# Audio_SCHEMATIC.net
KiCad netlist of a schematic drawn in Altium Designer
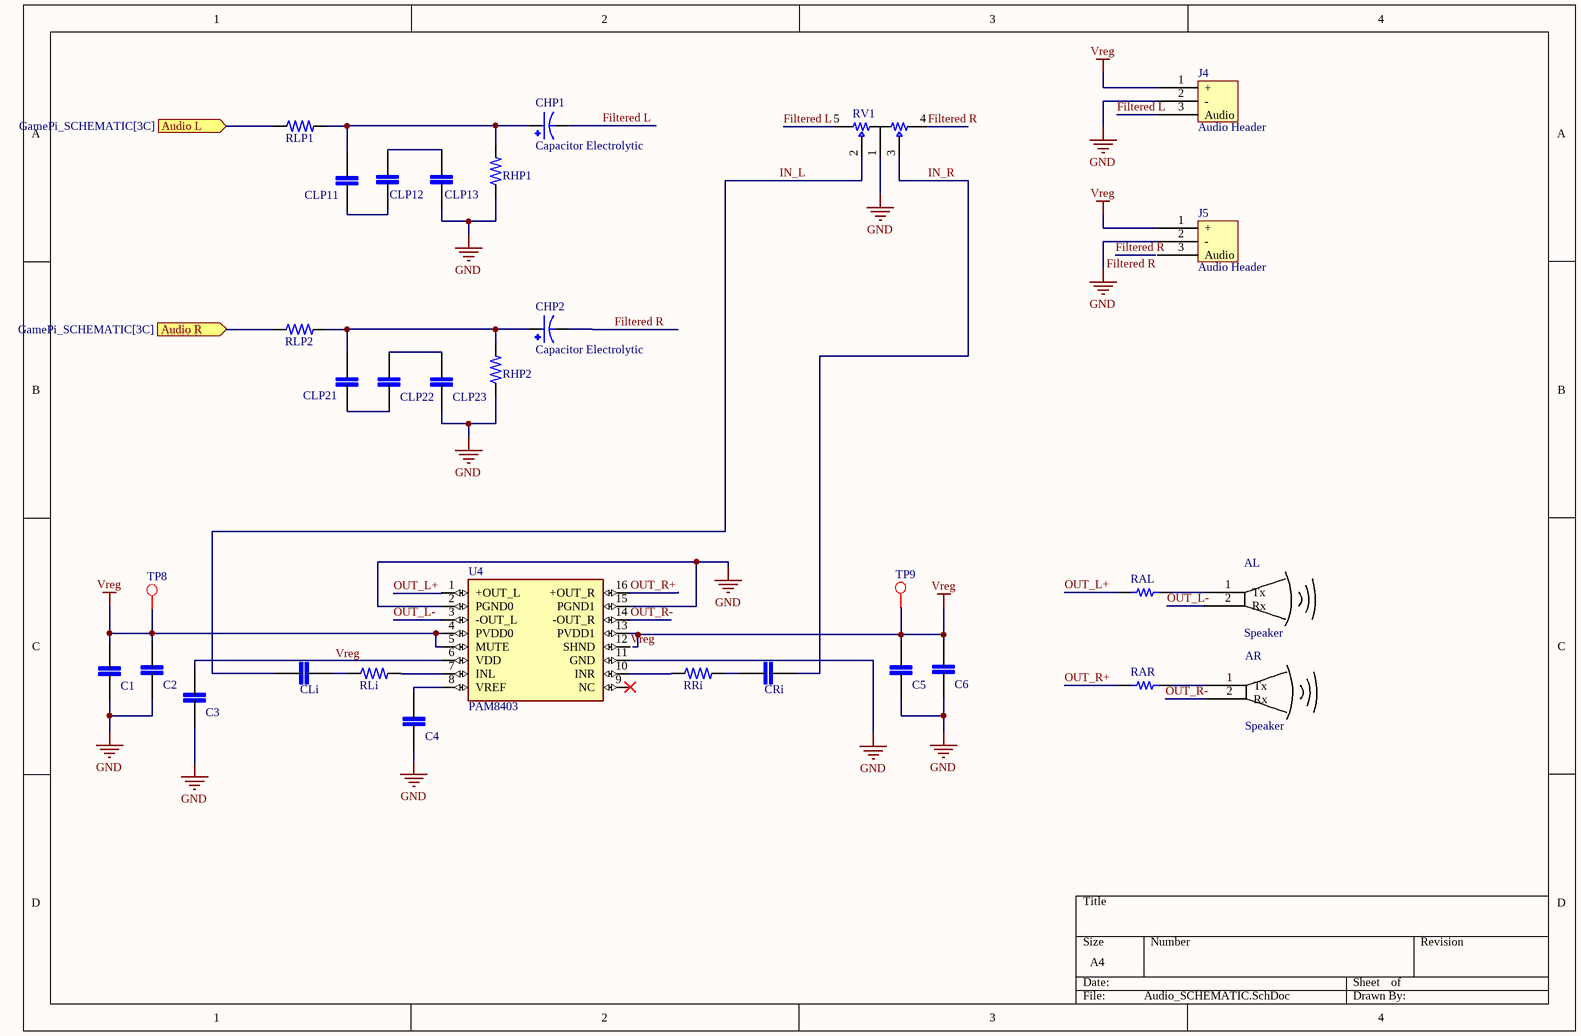
[diagram p0: Audio_SCHEMATIC.SchDoc]

(export (version "E")
  (design (tool "Eeschema 10.0.6"))
  (components
    (comp (ref "AL")
      (value "Speaker")
      (footprint "Speaker")
      (libsource (lib "GamePi SCH LIB") (part "Speaker"))
    )
    (comp (ref "AR")
      (value "Speaker")
      (footprint "Speaker")
      (libsource (lib "GamePi SCH LIB") (part "Speaker"))
    )
    (comp (ref "C1")
      (value "0805")
      (footprint "Capacitor 0805")
      (libsource (lib "GamePi SCH LIB") (part "Capacitor 0805"))
    )
    (comp (ref "C2")
      (value "0805")
      (footprint "Capacitor 0805")
      (libsource (lib "GamePi SCH LIB") (part "Capacitor 0805"))
    )
    (comp (ref "C3")
      (value "0805")
      (footprint "Capacitor 0805")
      (libsource (lib "GamePi SCH LIB") (part "Capacitor 0805"))
    )
    (comp (ref "C4")
      (value "0805")
      (footprint "Capacitor 0805")
      (libsource (lib "GamePi SCH LIB") (part "Capacitor 0805"))
    )
    (comp (ref "C5")
      (value "0805")
      (footprint "Capacitor 0805")
      (libsource (lib "GamePi SCH LIB") (part "Capacitor 0805"))
    )
    (comp (ref "C6")
      (value "0805")
      (footprint "Capacitor 0805")
      (libsource (lib "GamePi SCH LIB") (part "Capacitor 0805"))
    )
    (comp (ref "CHP1")
      (value "Capacitor Electrolytic")
      (footprint "Capacitor Electrolytic")
      (libsource (lib "GamePi SCH LIB") (part "Capacitor Electrolytic"))
    )
    (comp (ref "CHP2")
      (value "Capacitor Electrolytic")
      (footprint "Capacitor Electrolytic")
      (libsource (lib "GamePi SCH LIB") (part "Capacitor Electrolytic"))
    )
    (comp (ref "CLi")
      (value "0805")
      (footprint "Capacitor 0805")
      (libsource (lib "GamePi") (part "Capacitor 0805"))
    )
    (comp (ref "CLP11")
      (value "0805")
      (footprint "Capacitor 0805")
      (libsource (lib "GamePi SCH LIB") (part "Capacitor 0805"))
    )
    (comp (ref "CLP12")
      (value "0805")
      (footprint "Capacitor 0805")
      (libsource (lib "GamePi SCH LIB") (part "Capacitor 0805"))
    )
    (comp (ref "CLP13")
      (value "0805")
      (footprint "Capacitor 0805")
      (libsource (lib "GamePi SCH LIB") (part "Capacitor 0805"))
    )
    (comp (ref "CLP21")
      (value "0805")
      (footprint "Capacitor 0805")
      (libsource (lib "GamePi SCH LIB") (part "Capacitor 0805"))
    )
    (comp (ref "CLP22")
      (value "0805")
      (footprint "Capacitor 0805")
      (libsource (lib "GamePi SCH LIB") (part "Capacitor 0805"))
    )
    (comp (ref "CLP23")
      (value "0805")
      (footprint "Capacitor 0805")
      (libsource (lib "GamePi SCH LIB") (part "Capacitor 0805"))
    )
    (comp (ref "CRi")
      (value "0805")
      (footprint "Capacitor 0805")
      (libsource (lib "GamePi") (part "Capacitor 0805"))
    )
    (comp (ref "J4")
      (value "Audio Header")
      (footprint "Audio Header")
      (libsource (lib "GamePi SCH LIB") (part "Audio Header"))
    )
    (comp (ref "J5")
      (value "Audio Header")
      (footprint "Audio Header")
      (libsource (lib "GamePi SCH LIB") (part "Audio Header"))
    )
    (comp (ref "RAL")
      (value "Resistor Axial")
      (footprint "Resistor Axial")
      (libsource (lib "GamePi SCH LIB") (part "Resistor Axial"))
    )
    (comp (ref "RAR")
      (value "Resistor Axial")
      (footprint "Resistor Axial")
      (libsource (lib "GamePi SCH LIB") (part "Resistor Axial"))
    )
    (comp (ref "RHP1")
      (value "0805")
      (footprint "Resistor 0805")
      (libsource (lib "GamePi SCH LIB") (part "Resistor 0805"))
    )
    (comp (ref "RHP2")
      (value "0805")
      (footprint "Resistor 0805")
      (libsource (lib "GamePi SCH LIB") (part "Resistor 0805"))
    )
    (comp (ref "RLi")
      (value "0805")
      (footprint "Resistor 0805")
      (libsource (lib "GamePi") (part "Resistor 0805"))
    )
    (comp (ref "RLP1")
      (value "0805")
      (footprint "Resistor 0805")
      (libsource (lib "GamePi SCH LIB") (part "Resistor 0805"))
    )
    (comp (ref "RLP2")
      (value "0805")
      (footprint "Resistor 0805")
      (libsource (lib "GamePi SCH LIB") (part "Resistor 0805"))
    )
    (comp (ref "RRi")
      (value "0805")
      (footprint "Resistor 0805")
      (libsource (lib "GamePi") (part "Resistor 0805"))
    )
    (comp (ref "RV1")
      (value "B103 Potentiometer Wheel")
      (footprint "B103 Pot Wheel")
      (libsource (lib "GamePi SCH LIB") (part "B103 Potentiometer Wheel"))
    )
    (comp (ref "TP8")
      (value "Test Point")
      (footprint "Test Point")
      (libsource (lib "GamePi SCH LIB") (part "Test Point"))
    )
    (comp (ref "TP9")
      (value "Test Point")
      (footprint "Test Point")
      (libsource (lib "GamePi SCH LIB") (part "Test Point"))
    )
    (comp (ref "U4")
      (value "PAM8403")
      (footprint "PAM8403")
      (libsource (lib "GamePi SCH LIB") (part "PAM8403"))
    )
  )
  (nets
    (net (code "1") (name "/Audio L") (class "Default")
      (node (ref "RLP1") (pin "1") (pinfunction "1_1") (pintype "passive"))
    )
    (net (code "2") (name "/Audio R") (class "Default")
      (node (ref "RLP2") (pin "1") (pinfunction "1_1") (pintype "passive"))
    )
    (net (code "3") (name "/Filtered L") (class "Default")
      (node (ref "CHP1") (pin "N") (pinfunction "N_N") (pintype "passive"))
      (node (ref "J4") (pin "3") (pinfunction "Audio_3") (pintype "passive"))
      (node (ref "RV1") (pin "5") (pinfunction "5_5") (pintype "passive"))
    )
    (net (code "4") (name "/Filtered R") (class "Default")
      (node (ref "CHP2") (pin "N") (pinfunction "N_N") (pintype "passive"))
      (node (ref "J5") (pin "3") (pinfunction "Audio_3") (pintype "passive"))
      (node (ref "RV1") (pin "4") (pinfunction "4_4") (pintype "passive"))
    )
    (net (code "5") (name "/IN_L") (class "Default")
      (node (ref "CLi") (pin "1") (pinfunction "1_1") (pintype "passive"))
      (node (ref "RV1") (pin "2") (pinfunction "2_2") (pintype "passive"))
    )
    (net (code "6") (name "/IN_R") (class "Default")
      (node (ref "CRi") (pin "2") (pinfunction "2_2") (pintype "passive"))
      (node (ref "RV1") (pin "3") (pinfunction "3_3") (pintype "passive"))
    )
    (net (code "7") (name "/OUT_L+") (class "Default")
      (node (ref "RAL") (pin "1") (pinfunction "1_1") (pintype "passive"))
      (node (ref "U4") (pin "1") (pinfunction "+OUT_L_1") (pintype "bidirectional"))
    )
    (net (code "8") (name "/OUT_L-") (class "Default")
      (node (ref "AL") (pin "2") (pinfunction "Rx_2") (pintype "passive"))
      (node (ref "U4") (pin "3") (pinfunction "-OUT_L_3") (pintype "bidirectional"))
    )
    (net (code "9") (name "/OUT_R+") (class "Default")
      (node (ref "RAR") (pin "1") (pinfunction "1_1") (pintype "passive"))
      (node (ref "U4") (pin "16") (pinfunction "+OUT_R_16") (pintype "bidirectional"))
    )
    (net (code "10") (name "/OUT_R-") (class "Default")
      (node (ref "AR") (pin "2") (pinfunction "Rx_2") (pintype "passive"))
      (node (ref "U4") (pin "14") (pinfunction "-OUT_R_14") (pintype "bidirectional"))
    )
    (net (code "11") (name "GND") (class "Default")
      (node (ref "C1") (pin "1") (pinfunction "1_1") (pintype "passive"))
      (node (ref "C2") (pin "1") (pinfunction "1_1") (pintype "passive"))
      (node (ref "C3") (pin "1") (pinfunction "1_1") (pintype "passive"))
      (node (ref "C4") (pin "1") (pinfunction "1_1") (pintype "passive"))
      (node (ref "C5") (pin "1") (pinfunction "1_1") (pintype "passive"))
      (node (ref "C6") (pin "1") (pinfunction "1_1") (pintype "passive"))
      (node (ref "CLP13") (pin "1") (pinfunction "1_1") (pintype "passive"))
      (node (ref "CLP23") (pin "1") (pinfunction "1_1") (pintype "passive"))
      (node (ref "J4") (pin "2") (pinfunction "-_2") (pintype "passive"))
      (node (ref "J5") (pin "2") (pinfunction "-_2") (pintype "passive"))
      (node (ref "RHP1") (pin "1") (pinfunction "1_1") (pintype "passive"))
      (node (ref "RHP2") (pin "1") (pinfunction "1_1") (pintype "passive"))
      (node (ref "RV1") (pin "1") (pinfunction "1_1") (pintype "passive"))
      (node (ref "U4") (pin "11") (pinfunction "GND_11") (pintype "bidirectional"))
      (node (ref "U4") (pin "15") (pinfunction "PGND1_15") (pintype "bidirectional"))
      (node (ref "U4") (pin "2") (pinfunction "PGND0_2") (pintype "bidirectional"))
    )
    (net (code "12") (name "Net-(AL-Tx)") (class "Default")
      (node (ref "AL") (pin "1") (pinfunction "Tx_1") (pintype "passive"))
      (node (ref "RAL") (pin "2") (pinfunction "2_2") (pintype "passive"))
    )
    (net (code "13") (name "Net-(AR-Tx)") (class "Default")
      (node (ref "AR") (pin "1") (pinfunction "Tx_1") (pintype "passive"))
      (node (ref "RAR") (pin "2") (pinfunction "2_2") (pintype "passive"))
    )
    (net (code "14") (name "Net-(CHP1-PadP)") (class "Default")
      (node (ref "CHP1") (pin "P") (pinfunction "P_P") (pintype "passive"))
      (node (ref "CLP11") (pin "2") (pinfunction "2_2") (pintype "passive"))
      (node (ref "RHP1") (pin "2") (pinfunction "2_2") (pintype "passive"))
      (node (ref "RLP1") (pin "2") (pinfunction "2_2") (pintype "passive"))
    )
    (net (code "15") (name "Net-(CHP2-PadP)") (class "Default")
      (node (ref "CHP2") (pin "P") (pinfunction "P_P") (pintype "passive"))
      (node (ref "CLP21") (pin "2") (pinfunction "2_2") (pintype "passive"))
      (node (ref "RHP2") (pin "2") (pinfunction "2_2") (pintype "passive"))
      (node (ref "RLP2") (pin "2") (pinfunction "2_2") (pintype "passive"))
    )
    (net (code "16") (name "Net-(CLP11-Pad1)") (class "Default")
      (node (ref "CLP11") (pin "1") (pinfunction "1_1") (pintype "passive"))
      (node (ref "CLP12") (pin "1") (pinfunction "1_1") (pintype "passive"))
    )
    (net (code "17") (name "Net-(CLP12-Pad2)") (class "Default")
      (node (ref "CLP12") (pin "2") (pinfunction "2_2") (pintype "passive"))
      (node (ref "CLP13") (pin "2") (pinfunction "2_2") (pintype "passive"))
    )
    (net (code "18") (name "Net-(CLP21-Pad1)") (class "Default")
      (node (ref "CLP21") (pin "1") (pinfunction "1_1") (pintype "passive"))
      (node (ref "CLP22") (pin "1") (pinfunction "1_1") (pintype "passive"))
    )
    (net (code "19") (name "Net-(CLP22-Pad2)") (class "Default")
      (node (ref "CLP22") (pin "2") (pinfunction "2_2") (pintype "passive"))
      (node (ref "CLP23") (pin "2") (pinfunction "2_2") (pintype "passive"))
    )
    (net (code "20") (name "Net-(CLi-Pad2)") (class "Default")
      (node (ref "CLi") (pin "2") (pinfunction "2_2") (pintype "passive"))
      (node (ref "RLi") (pin "1") (pinfunction "1_1") (pintype "passive"))
    )
    (net (code "21") (name "Net-(CRi-Pad1)") (class "Default")
      (node (ref "CRi") (pin "1") (pinfunction "1_1") (pintype "passive"))
      (node (ref "RRi") (pin "2") (pinfunction "2_2") (pintype "passive"))
    )
    (net (code "22") (name "Net-(U4-INL)") (class "Default")
      (node (ref "RLi") (pin "2") (pinfunction "2_2") (pintype "passive"))
      (node (ref "U4") (pin "7") (pinfunction "INL_7") (pintype "bidirectional"))
    )
    (net (code "23") (name "Net-(U4-INR)") (class "Default")
      (node (ref "RRi") (pin "1") (pinfunction "1_1") (pintype "passive"))
      (node (ref "U4") (pin "10") (pinfunction "INR_10") (pintype "bidirectional"))
    )
    (net (code "24") (name "Net-(U4-VDD)") (class "Default")
      (node (ref "C3") (pin "2") (pinfunction "2_2") (pintype "passive"))
      (node (ref "U4") (pin "6") (pinfunction "VDD_6") (pintype "bidirectional"))
    )
    (net (code "25") (name "Net-(U4-VREF)") (class "Default")
      (node (ref "C4") (pin "2") (pinfunction "2_2") (pintype "passive"))
      (node (ref "U4") (pin "8") (pinfunction "VREF_8") (pintype "bidirectional"))
    )
    (net (code "26") (name "Vreg") (class "Default")
      (node (ref "C1") (pin "2") (pinfunction "2_2") (pintype "passive"))
      (node (ref "C2") (pin "2") (pinfunction "2_2") (pintype "passive"))
      (node (ref "C5") (pin "2") (pinfunction "2_2") (pintype "passive"))
      (node (ref "C6") (pin "2") (pinfunction "2_2") (pintype "passive"))
      (node (ref "J4") (pin "1") (pinfunction "+_1") (pintype "passive"))
      (node (ref "J5") (pin "1") (pinfunction "+_1") (pintype "passive"))
      (node (ref "TP8") (pin "TP?") (pinfunction "Test_Point_TP?") (pintype "passive"))
      (node (ref "TP9") (pin "TP?") (pinfunction "Test_Point_TP?") (pintype "passive"))
      (node (ref "U4") (pin "12") (pinfunction "SHND_12") (pintype "bidirectional"))
      (node (ref "U4") (pin "13") (pinfunction "PVDD1_13") (pintype "bidirectional"))
      (node (ref "U4") (pin "4") (pinfunction "PVDD0_4") (pintype "bidirectional"))
      (node (ref "U4") (pin "5") (pinfunction "MUTE_5") (pintype "bidirectional"))
    )
    (net (code "27") (name "unconnected-(U4-NC-Pad9)") (class "Default")
      (node (ref "U4") (pin "9") (pinfunction "NC_9") (pintype "bidirectional+no_connect"))
    )
  )
)
